# Grove_-_Magnetic_Switch_v1_3.net
KiCad netlist of a schematic drawn in EAGLE
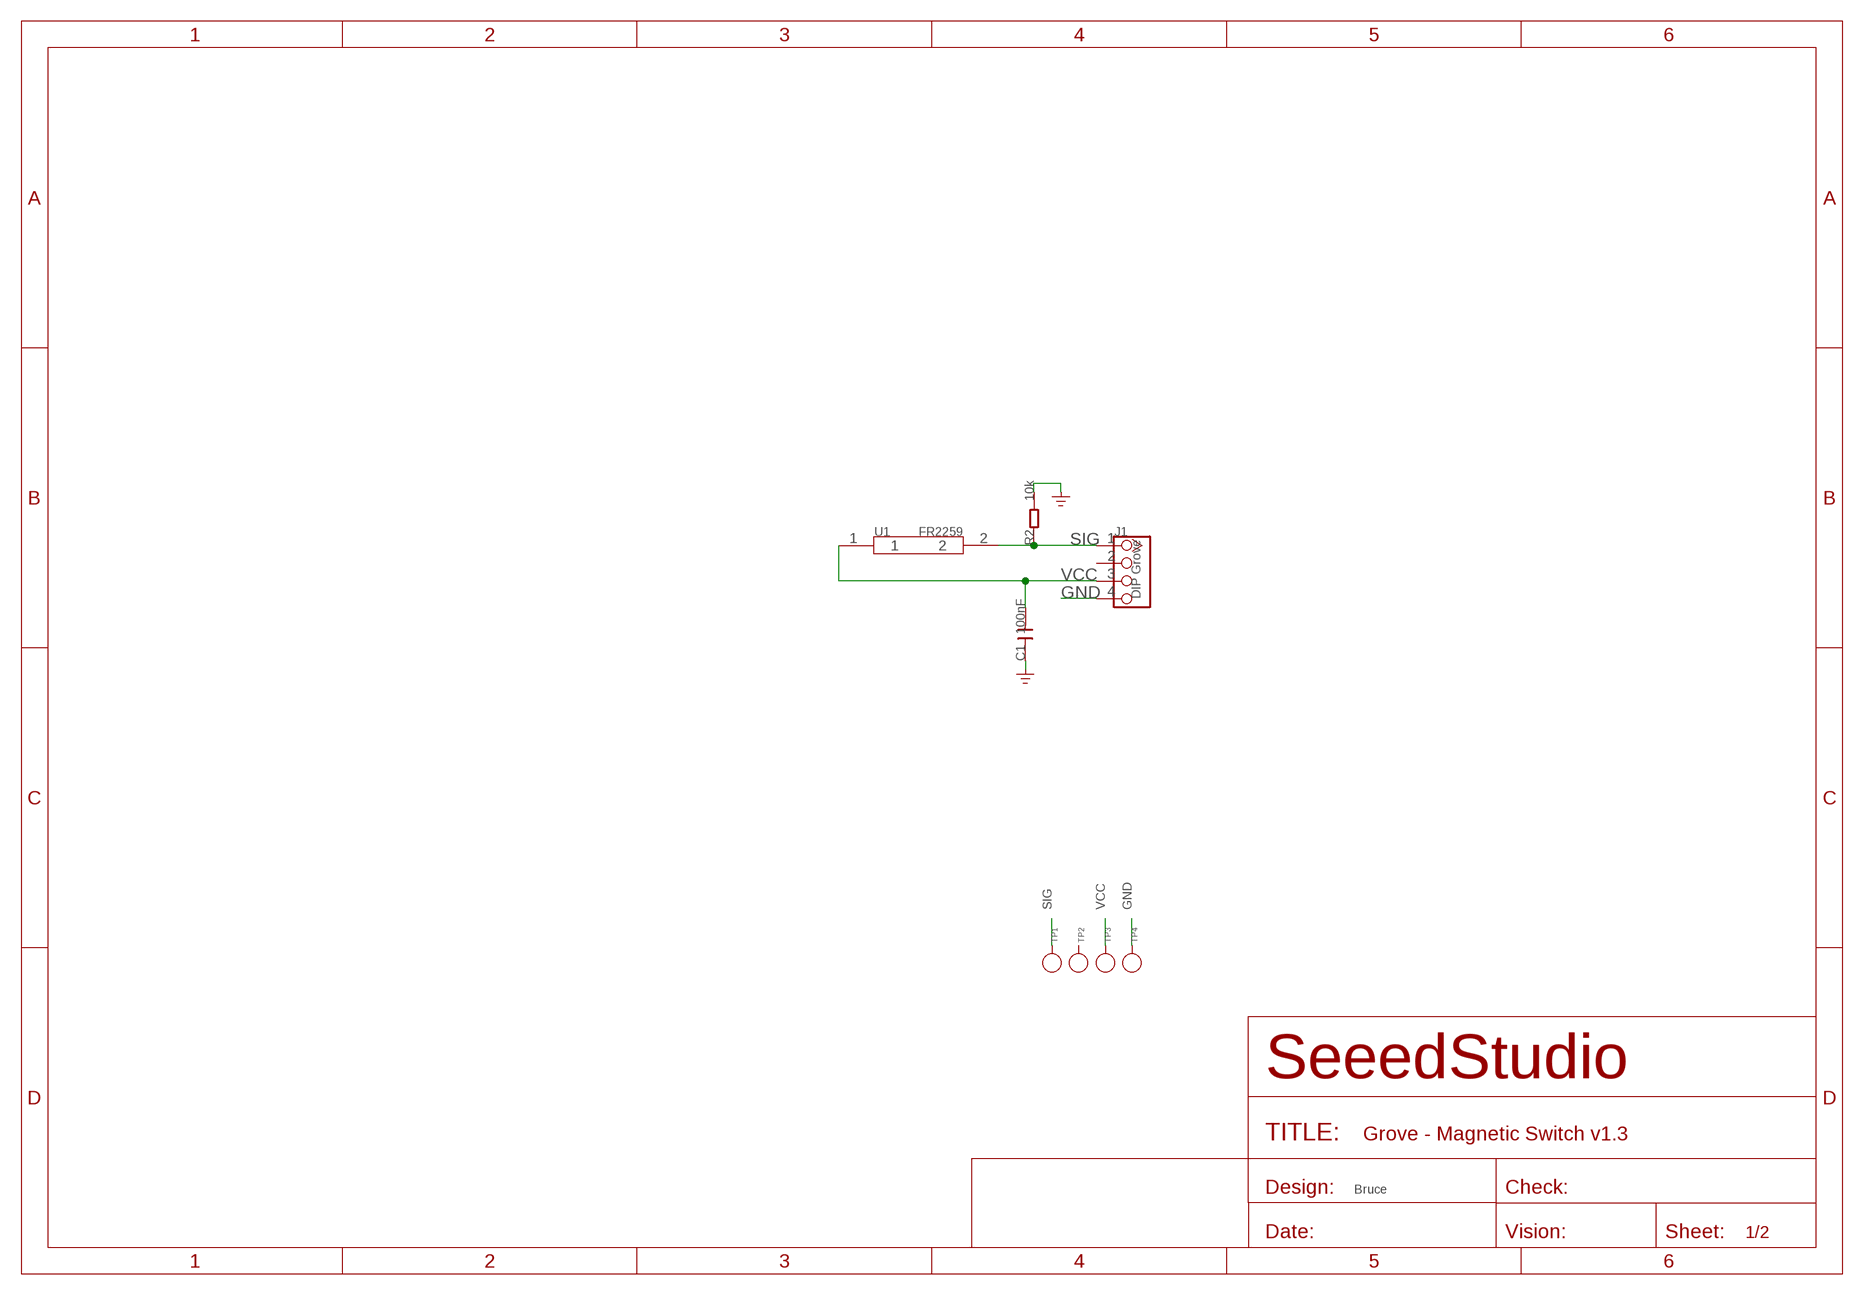
[diagram p0: schematic, sheet 1]
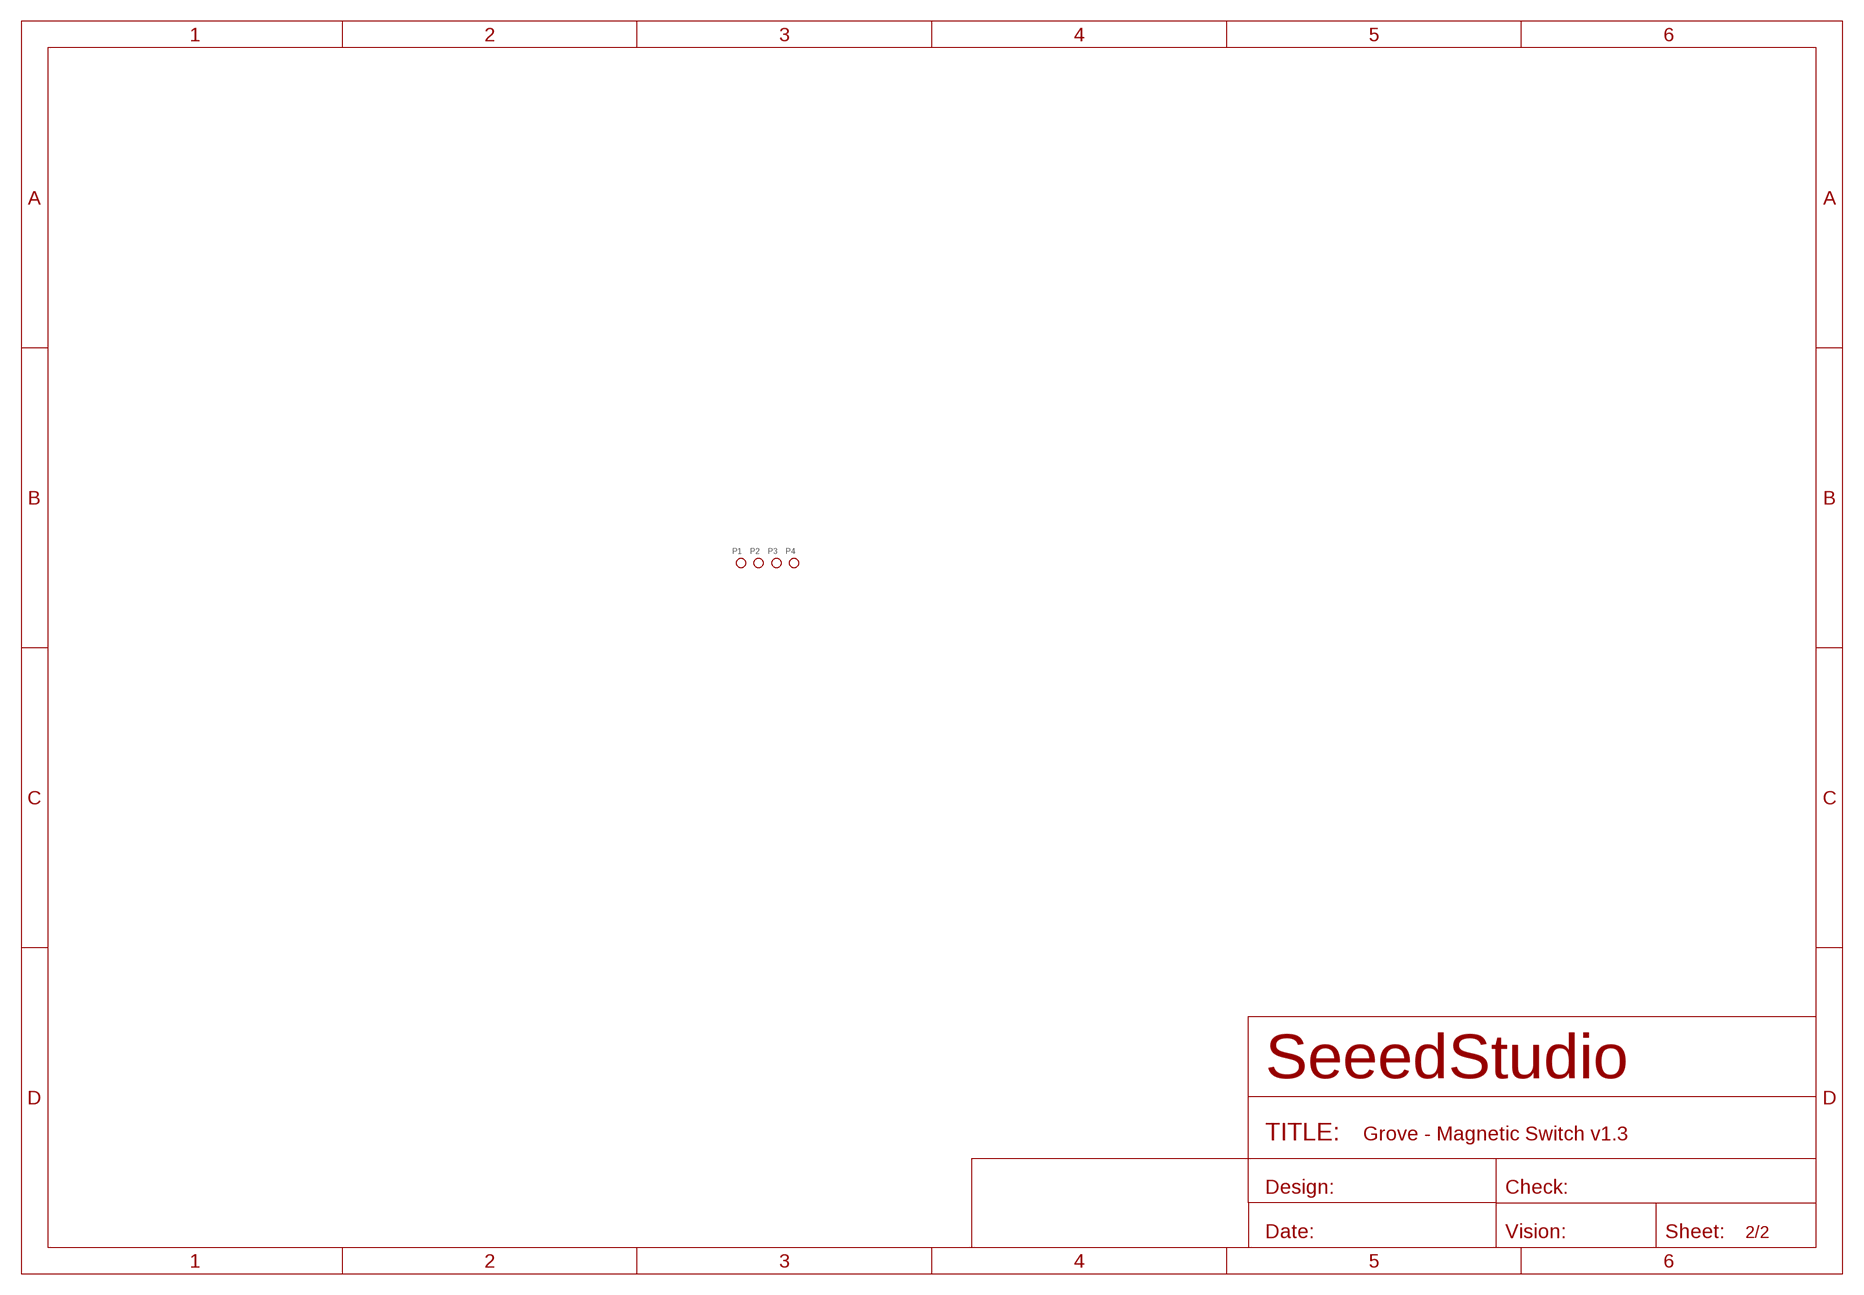
[diagram p1: schematic, sheet 2]

(export (version "E")
  (design (tool "Eeschema 10.0.6"))
  (components
    (comp (ref "P1")
      (value "PAD-MARK")
      (footprint "eagle-import:ROUND-MARK-1.0")
      (fields (field (name "PARTNO") "DNP"))
      (libsource (lib "eagle-import") (part "PAD-MARK"))
    )
    (comp (ref "P2")
      (value "PAD-MARK")
      (footprint "eagle-import:ROUND-MARK-1.0")
      (fields (field (name "PARTNO") "DNP"))
      (libsource (lib "eagle-import") (part "PAD-MARK"))
    )
    (comp (ref "P3")
      (value "PAD-MARK")
      (footprint "eagle-import:ROUND-MARK-1.0")
      (fields (field (name "PARTNO") "DNP"))
      (libsource (lib "eagle-import") (part "PAD-MARK"))
    )
    (comp (ref "P4")
      (value "PAD-MARK")
      (footprint "eagle-import:ROUND-MARK-1.0")
      (fields (field (name "PARTNO") "DNP"))
      (libsource (lib "eagle-import") (part "PAD-MARK"))
    )
    (comp (ref "C1")
      (value "100nF")
      (footprint "eagle-import:C0603")
      (libsource (lib "eagle-import") (part "C-0603"))
    )
    (comp (ref "J1")
      (value "DIP Grove")
      (footprint "eagle-import:4P-2.0")
      (libsource (lib "eagle-import") (part "TWIG-4P-2.0-2.0"))
    )
    (comp (ref "R2")
      (value "10k")
      (footprint "eagle-import:R0603")
      (libsource (lib "eagle-import") (part "R-0603"))
    )
    (comp (ref "TP1")
      (value "PAD-TEST-POINT'4545'")
      (footprint "eagle-import:TP_4545")
      (fields (field (name "PARTNO") "DNP"))
      (libsource (lib "eagle-import") (part "PAD-TEST-POINT'4545'"))
    )
    (comp (ref "TP2")
      (value "PAD-TEST-POINT'4545'")
      (footprint "eagle-import:TP_4545")
      (fields (field (name "PARTNO") "DNP"))
      (libsource (lib "eagle-import") (part "PAD-TEST-POINT'4545'"))
    )
    (comp (ref "TP3")
      (value "PAD-TEST-POINT'4545'")
      (footprint "eagle-import:TP_4545")
      (fields (field (name "PARTNO") "DNP"))
      (libsource (lib "eagle-import") (part "PAD-TEST-POINT'4545'"))
    )
    (comp (ref "TP4")
      (value "PAD-TEST-POINT'4545'")
      (footprint "eagle-import:TP_4545")
      (fields (field (name "PARTNO") "DNP"))
      (libsource (lib "eagle-import") (part "PAD-TEST-POINT'4545'"))
    )
    (comp (ref "U1")
      (value "FR2259")
      (footprint "eagle-import:MAGNETISM")
      (libsource (lib "eagle-import") (part "MAGNETISM"))
    )
  )
  (nets
    (net (code "1") (name "GND") (class "Default")
      (node (ref "C1") (pin "1") (pinfunction "1_1") (pintype "passive"))
      (node (ref "J1") (pin "4") (pinfunction "4_4") (pintype "bidirectional"))
      (node (ref "R2") (pin "2") (pinfunction "2_2") (pintype "passive"))
      (node (ref "TP4") (pin "T") (pinfunction "T_T") (pintype "bidirectional"))
    )
    (net (code "2") (name "SIG") (class "Default")
      (node (ref "J1") (pin "1") (pinfunction "1_1") (pintype "bidirectional"))
      (node (ref "R2") (pin "1") (pinfunction "1_1") (pintype "passive"))
      (node (ref "TP1") (pin "T") (pinfunction "T_T") (pintype "bidirectional"))
      (node (ref "U1") (pin "2") (pinfunction "2_2") (pintype "bidirectional"))
    )
    (net (code "3") (name "VCC") (class "Default")
      (node (ref "C1") (pin "2") (pinfunction "2_2") (pintype "passive"))
      (node (ref "J1") (pin "3") (pinfunction "3_3") (pintype "bidirectional"))
      (node (ref "TP3") (pin "T") (pinfunction "T_T") (pintype "bidirectional"))
      (node (ref "U1") (pin "1") (pinfunction "1_1") (pintype "bidirectional"))
    )
    (net (code "4") (name "unconnected-(J1-Pad2)") (class "Default")
      (node (ref "J1") (pin "2") (pinfunction "2_2") (pintype "bidirectional"))
    )
    (net (code "5") (name "unconnected-(TP2-PadT)") (class "Default")
      (node (ref "TP2") (pin "T") (pinfunction "T_T") (pintype "bidirectional"))
    )
  )
)
